# RP_Pico.net
KiCad netlist of a schematic drawn in Altium Designer
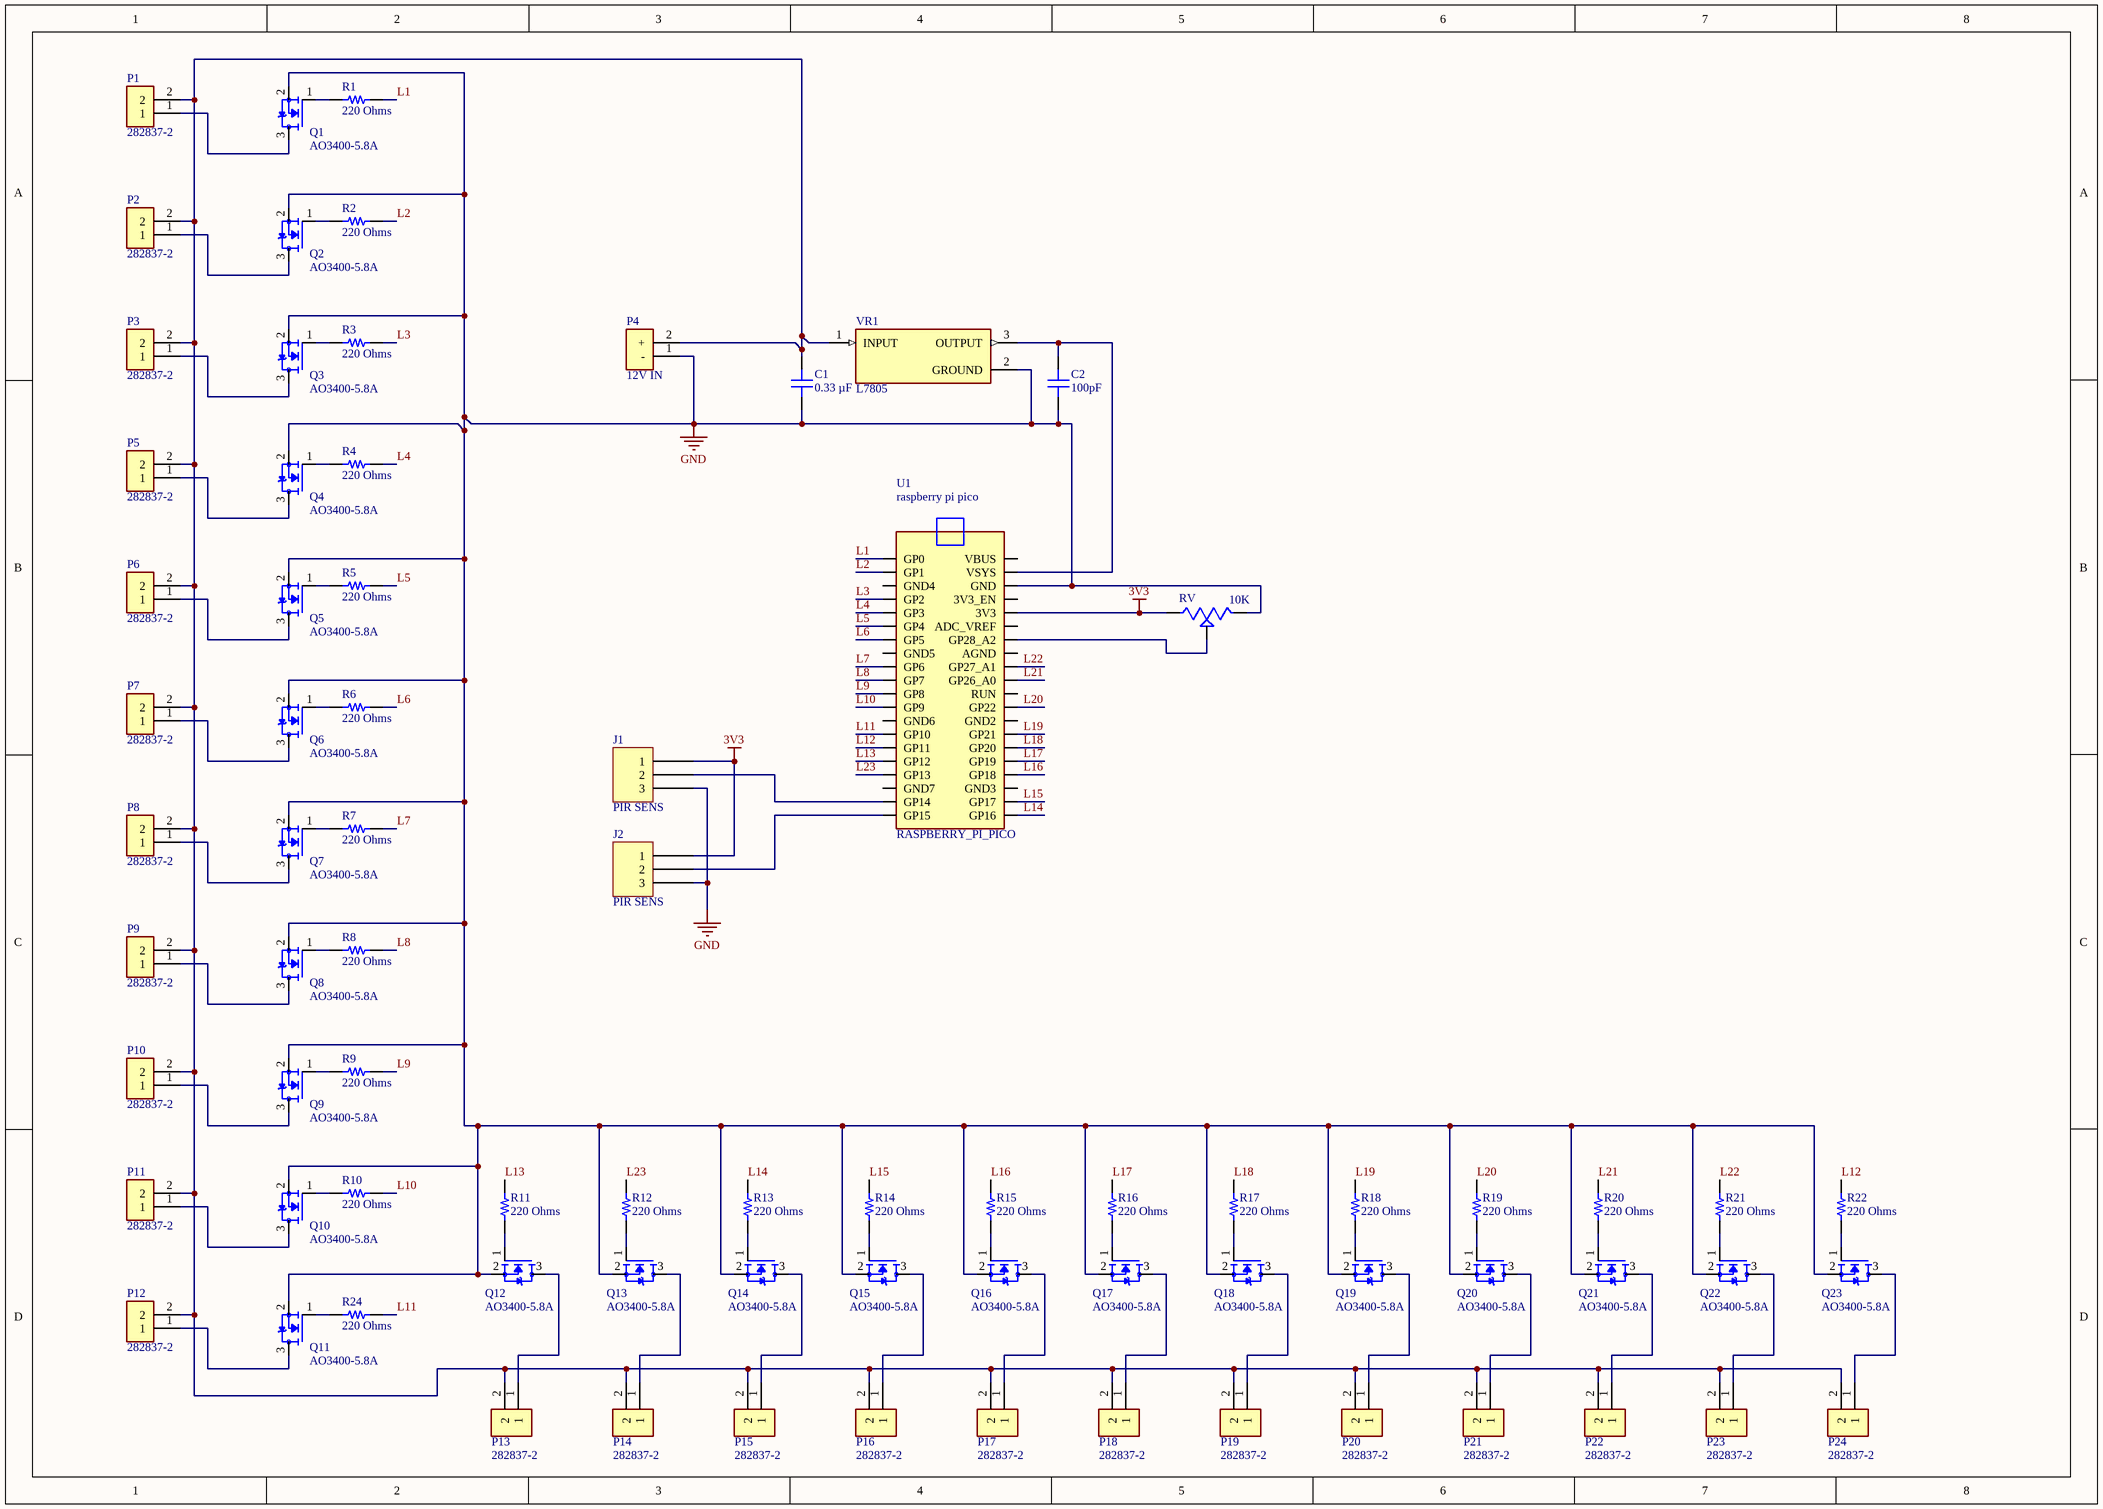
[diagram p0: RP Pico.SchDoc]

(export (version "E")
  (design (tool "Eeschema 10.0.6"))
  (components
    (comp (ref "C1")
      (value "0.33 µF")
      (footprint "CAP 1206_3216 - 0.8MM")
      (description "CAP CER 0.33UF 25V X7R 1206")
      (fields
        (field (name "PART NUMBER") "CC1206JKX7R8BB334")
        (field (name "CAPACITANCE") "0.33 µF")
        (field (name "MANUFACTURER") "Yageo")
      )
      (libsource (lib "Celestial Altium Library - altium_library") (part "Capacitor"))
    )
    (comp (ref "C2")
      (value "100pF")
      (footprint "CAP 1206_3216 - 0.8MM")
      (description "CAP CER 100PF 100V C0G/NP0 1206")
      (fields
        (field (name "PART NUMBER") "MM061A101JCT2A")
        (field (name "CAPACITANCE") "100pF")
        (field (name "MANUFACTURER") "AVX Corporation")
      )
      (libsource (lib "Celestial Altium Library - altium_library") (part "Capacitor"))
    )
    (comp (ref "J1")
      (value "PIR SENS")
      (footprint "HARWIN M20-7820345")
      (description "CONN RCPT 3POS 0.1 GOLD PCB")
      (fields (field (name "PART NUMBER") "M20-7820342") (field (name "MANUFACTURER") "Harwin Inc."))
      (libsource (lib "Celestial Altium Library - altium_library") (part "3 Pin"))
    )
    (comp (ref "J2")
      (value "PIR SENS")
      (footprint "HARWIN M20-7820345")
      (description "CONN RCPT 3POS 0.1 GOLD PCB")
      (fields (field (name "PART NUMBER") "M20-7820342") (field (name "MANUFACTURER") "Harwin Inc."))
      (libsource (lib "Celestial Altium Library - altium_library") (part "3 Pin"))
    )
    (comp (ref "P1")
      (value "282837-2")
      (footprint "TE_282837-2")
      (fields (field (name "MF") "TE Connectivity"))
      (libsource (lib "2 pin con") (part "282837-2"))
    )
    (comp (ref "P2")
      (value "282837-2")
      (footprint "TE_282837-2")
      (fields (field (name "MF") "TE Connectivity"))
      (libsource (lib "2 pin con") (part "282837-2"))
    )
    (comp (ref "P3")
      (value "282837-2")
      (footprint "TE_282837-2")
      (fields (field (name "MF") "TE Connectivity"))
      (libsource (lib "2 pin con") (part "282837-2"))
    )
    (comp (ref "P4")
      (value "12V IN")
      (footprint "TE_282837-2")
      (fields (field (name "MF") "TE Connectivity") (field (name "MP") "282837-2"))
      (libsource (lib "2 pin con") (part "282837-2"))
    )
    (comp (ref "P5")
      (value "282837-2")
      (footprint "TE_282837-2")
      (fields (field (name "MF") "TE Connectivity"))
      (libsource (lib "2 pin con") (part "282837-2"))
    )
    (comp (ref "P6")
      (value "282837-2")
      (footprint "TE_282837-2")
      (fields (field (name "MF") "TE Connectivity"))
      (libsource (lib "2 pin con") (part "282837-2"))
    )
    (comp (ref "P7")
      (value "282837-2")
      (footprint "TE_282837-2")
      (fields (field (name "MF") "TE Connectivity"))
      (libsource (lib "2 pin con") (part "282837-2"))
    )
    (comp (ref "P8")
      (value "282837-2")
      (footprint "TE_282837-2")
      (fields (field (name "MF") "TE Connectivity"))
      (libsource (lib "2 pin con") (part "282837-2"))
    )
    (comp (ref "P9")
      (value "282837-2")
      (footprint "TE_282837-2")
      (fields (field (name "MF") "TE Connectivity"))
      (libsource (lib "2 pin con") (part "282837-2"))
    )
    (comp (ref "P10")
      (value "282837-2")
      (footprint "TE_282837-2")
      (fields (field (name "MF") "TE Connectivity"))
      (libsource (lib "2 pin con") (part "282837-2"))
    )
    (comp (ref "P11")
      (value "282837-2")
      (footprint "TE_282837-2")
      (fields (field (name "MF") "TE Connectivity"))
      (libsource (lib "2 pin con") (part "282837-2"))
    )
    (comp (ref "P12")
      (value "282837-2")
      (footprint "TE_282837-2")
      (fields (field (name "MF") "TE Connectivity"))
      (libsource (lib "2 pin con") (part "282837-2"))
    )
    (comp (ref "P13")
      (value "282837-2")
      (footprint "TE_282837-2")
      (fields (field (name "MF") "TE Connectivity"))
      (libsource (lib "") (part "282837-2_1"))
    )
    (comp (ref "P14")
      (value "282837-2")
      (footprint "TE_282837-2")
      (fields (field (name "MF") "TE Connectivity"))
      (libsource (lib "") (part "282837-2_1"))
    )
    (comp (ref "P15")
      (value "282837-2")
      (footprint "TE_282837-2")
      (fields (field (name "MF") "TE Connectivity"))
      (libsource (lib "") (part "282837-2_1"))
    )
    (comp (ref "P16")
      (value "282837-2")
      (footprint "TE_282837-2")
      (fields (field (name "MF") "TE Connectivity"))
      (libsource (lib "") (part "282837-2_1"))
    )
    (comp (ref "P17")
      (value "282837-2")
      (footprint "TE_282837-2")
      (fields (field (name "MF") "TE Connectivity"))
      (libsource (lib "") (part "282837-2_1"))
    )
    (comp (ref "P18")
      (value "282837-2")
      (footprint "TE_282837-2")
      (fields (field (name "MF") "TE Connectivity"))
      (libsource (lib "") (part "282837-2_1"))
    )
    (comp (ref "P19")
      (value "282837-2")
      (footprint "TE_282837-2")
      (fields (field (name "MF") "TE Connectivity"))
      (libsource (lib "") (part "282837-2_1"))
    )
    (comp (ref "P20")
      (value "282837-2")
      (footprint "TE_282837-2")
      (fields (field (name "MF") "TE Connectivity"))
      (libsource (lib "") (part "282837-2_1"))
    )
    (comp (ref "P21")
      (value "282837-2")
      (footprint "TE_282837-2")
      (fields (field (name "MF") "TE Connectivity"))
      (libsource (lib "") (part "282837-2_1"))
    )
    (comp (ref "P22")
      (value "282837-2")
      (footprint "TE_282837-2")
      (fields (field (name "MF") "TE Connectivity"))
      (libsource (lib "") (part "282837-2_1"))
    )
    (comp (ref "P23")
      (value "282837-2")
      (footprint "TE_282837-2")
      (fields (field (name "MF") "TE Connectivity"))
      (libsource (lib "") (part "282837-2_1"))
    )
    (comp (ref "P24")
      (value "282837-2")
      (footprint "TE_282837-2")
      (fields (field (name "MF") "TE Connectivity"))
      (libsource (lib "") (part "282837-2_1"))
    )
    (comp (ref "Q1")
      (value "AO3400-5.8A")
      (footprint "SOT95P260X140-3N")
      (description "N-Channel 30 V 5.8A (Ta) 1.5W (Ta) Surface Mount SOT-23")
      (fields (field (name "MF") "MDD"))
      (libsource (lib "AO3400-5.8A") (part "AO3400-5.8A"))
    )
    (comp (ref "Q2")
      (value "AO3400-5.8A")
      (footprint "SOT95P260X140-3N")
      (description "N-Channel 30 V 5.8A (Ta) 1.5W (Ta) Surface Mount SOT-23")
      (fields (field (name "MF") "MDD"))
      (libsource (lib "AO3400-5.8A") (part "AO3400-5.8A"))
    )
    (comp (ref "Q3")
      (value "AO3400-5.8A")
      (footprint "SOT95P260X140-3N")
      (description "N-Channel 30 V 5.8A (Ta) 1.5W (Ta) Surface Mount SOT-23")
      (fields (field (name "MF") "MDD"))
      (libsource (lib "AO3400-5.8A") (part "AO3400-5.8A"))
    )
    (comp (ref "Q4")
      (value "AO3400-5.8A")
      (footprint "SOT95P260X140-3N")
      (description "N-Channel 30 V 5.8A (Ta) 1.5W (Ta) Surface Mount SOT-23")
      (fields (field (name "MF") "MDD"))
      (libsource (lib "AO3400-5.8A") (part "AO3400-5.8A"))
    )
    (comp (ref "Q5")
      (value "AO3400-5.8A")
      (footprint "SOT95P260X140-3N")
      (description "N-Channel 30 V 5.8A (Ta) 1.5W (Ta) Surface Mount SOT-23")
      (fields (field (name "MF") "MDD"))
      (libsource (lib "AO3400-5.8A") (part "AO3400-5.8A"))
    )
    (comp (ref "Q6")
      (value "AO3400-5.8A")
      (footprint "SOT95P260X140-3N")
      (description "N-Channel 30 V 5.8A (Ta) 1.5W (Ta) Surface Mount SOT-23")
      (fields (field (name "MF") "MDD"))
      (libsource (lib "AO3400-5.8A") (part "AO3400-5.8A"))
    )
    (comp (ref "Q7")
      (value "AO3400-5.8A")
      (footprint "SOT95P260X140-3N")
      (description "N-Channel 30 V 5.8A (Ta) 1.5W (Ta) Surface Mount SOT-23")
      (fields (field (name "MF") "MDD"))
      (libsource (lib "AO3400-5.8A") (part "AO3400-5.8A"))
    )
    (comp (ref "Q8")
      (value "AO3400-5.8A")
      (footprint "SOT95P260X140-3N")
      (description "N-Channel 30 V 5.8A (Ta) 1.5W (Ta) Surface Mount SOT-23")
      (fields (field (name "MF") "MDD"))
      (libsource (lib "AO3400-5.8A") (part "AO3400-5.8A"))
    )
    (comp (ref "Q9")
      (value "AO3400-5.8A")
      (footprint "SOT95P260X140-3N")
      (description "N-Channel 30 V 5.8A (Ta) 1.5W (Ta) Surface Mount SOT-23")
      (fields (field (name "MF") "MDD"))
      (libsource (lib "AO3400-5.8A") (part "AO3400-5.8A"))
    )
    (comp (ref "Q10")
      (value "AO3400-5.8A")
      (footprint "SOT95P260X140-3N")
      (description "N-Channel 30 V 5.8A (Ta) 1.5W (Ta) Surface Mount SOT-23")
      (fields (field (name "MF") "MDD"))
      (libsource (lib "AO3400-5.8A") (part "AO3400-5.8A"))
    )
    (comp (ref "Q11")
      (value "AO3400-5.8A")
      (footprint "SOT95P260X140-3N")
      (description "N-Channel 30 V 5.8A (Ta) 1.5W (Ta) Surface Mount SOT-23")
      (fields (field (name "MF") "MDD"))
      (libsource (lib "AO3400-5.8A") (part "AO3400-5.8A"))
    )
    (comp (ref "Q12")
      (value "AO3400-5.8A")
      (footprint "SOT95P260X140-3N")
      (description "N-Channel 30 V 5.8A (Ta) 1.5W (Ta) Surface Mount SOT-23")
      (fields (field (name "MF") "MDD"))
      (libsource (lib "AO3400-5.8A") (part "AO3400-5.8A"))
    )
    (comp (ref "Q13")
      (value "AO3400-5.8A")
      (footprint "SOT95P260X140-3N")
      (description "N-Channel 30 V 5.8A (Ta) 1.5W (Ta) Surface Mount SOT-23")
      (fields (field (name "MF") "MDD"))
      (libsource (lib "AO3400-5.8A") (part "AO3400-5.8A"))
    )
    (comp (ref "Q14")
      (value "AO3400-5.8A")
      (footprint "SOT95P260X140-3N")
      (description "N-Channel 30 V 5.8A (Ta) 1.5W (Ta) Surface Mount SOT-23")
      (fields (field (name "MF") "MDD"))
      (libsource (lib "AO3400-5.8A") (part "AO3400-5.8A"))
    )
    (comp (ref "Q15")
      (value "AO3400-5.8A")
      (footprint "SOT95P260X140-3N")
      (description "N-Channel 30 V 5.8A (Ta) 1.5W (Ta) Surface Mount SOT-23")
      (fields (field (name "MF") "MDD"))
      (libsource (lib "AO3400-5.8A") (part "AO3400-5.8A"))
    )
    (comp (ref "Q16")
      (value "AO3400-5.8A")
      (footprint "SOT95P260X140-3N")
      (description "N-Channel 30 V 5.8A (Ta) 1.5W (Ta) Surface Mount SOT-23")
      (fields (field (name "MF") "MDD"))
      (libsource (lib "AO3400-5.8A") (part "AO3400-5.8A"))
    )
    (comp (ref "Q17")
      (value "AO3400-5.8A")
      (footprint "SOT95P260X140-3N")
      (description "N-Channel 30 V 5.8A (Ta) 1.5W (Ta) Surface Mount SOT-23")
      (fields (field (name "MF") "MDD"))
      (libsource (lib "AO3400-5.8A") (part "AO3400-5.8A"))
    )
    (comp (ref "Q18")
      (value "AO3400-5.8A")
      (footprint "SOT95P260X140-3N")
      (description "N-Channel 30 V 5.8A (Ta) 1.5W (Ta) Surface Mount SOT-23")
      (fields (field (name "MF") "MDD"))
      (libsource (lib "AO3400-5.8A") (part "AO3400-5.8A"))
    )
    (comp (ref "Q19")
      (value "AO3400-5.8A")
      (footprint "SOT95P260X140-3N")
      (description "N-Channel 30 V 5.8A (Ta) 1.5W (Ta) Surface Mount SOT-23")
      (fields (field (name "MF") "MDD"))
      (libsource (lib "AO3400-5.8A") (part "AO3400-5.8A"))
    )
    (comp (ref "Q20")
      (value "AO3400-5.8A")
      (footprint "SOT95P260X140-3N")
      (description "N-Channel 30 V 5.8A (Ta) 1.5W (Ta) Surface Mount SOT-23")
      (fields (field (name "MF") "MDD"))
      (libsource (lib "AO3400-5.8A") (part "AO3400-5.8A"))
    )
    (comp (ref "Q21")
      (value "AO3400-5.8A")
      (footprint "SOT95P260X140-3N")
      (description "N-Channel 30 V 5.8A (Ta) 1.5W (Ta) Surface Mount SOT-23")
      (fields (field (name "MF") "MDD"))
      (libsource (lib "AO3400-5.8A") (part "AO3400-5.8A"))
    )
    (comp (ref "Q22")
      (value "AO3400-5.8A")
      (footprint "SOT95P260X140-3N")
      (description "N-Channel 30 V 5.8A (Ta) 1.5W (Ta) Surface Mount SOT-23")
      (fields (field (name "MF") "MDD"))
      (libsource (lib "AO3400-5.8A") (part "AO3400-5.8A"))
    )
    (comp (ref "Q23")
      (value "AO3400-5.8A")
      (footprint "SOT95P260X140-3N")
      (description "N-Channel 30 V 5.8A (Ta) 1.5W (Ta) Surface Mount SOT-23")
      (fields (field (name "MF") "MDD"))
      (libsource (lib "AO3400-5.8A") (part "AO3400-5.8A"))
    )
    (comp (ref "R1")
      (value "220 Ohms")
      (footprint "YAGEO RES 1206_3216")
      (description "RES SMD 220 OHM 5% 1/4W 1206")
      (fields (field (name "PART NUMBER") "AC1206JR-07220RL") (field (name "MANUFACTURER") "Yageo"))
      (libsource (lib "Celestial Altium Library - altium_library") (part "Resistor"))
    )
    (comp (ref "R2")
      (value "220 Ohms")
      (footprint "YAGEO RES 1206_3216")
      (description "RES SMD 220 OHM 5% 1/4W 1206")
      (fields (field (name "PART NUMBER") "AC1206JR-07220RL") (field (name "MANUFACTURER") "Yageo"))
      (libsource (lib "Celestial Altium Library - altium_library") (part "Resistor"))
    )
    (comp (ref "R3")
      (value "220 Ohms")
      (footprint "YAGEO RES 1206_3216")
      (description "RES SMD 220 OHM 5% 1/4W 1206")
      (fields (field (name "PART NUMBER") "AC1206JR-07220RL") (field (name "MANUFACTURER") "Yageo"))
      (libsource (lib "Celestial Altium Library - altium_library") (part "Resistor"))
    )
    (comp (ref "R4")
      (value "220 Ohms")
      (footprint "YAGEO RES 1206_3216")
      (description "RES SMD 220 OHM 5% 1/4W 1206")
      (fields (field (name "PART NUMBER") "AC1206JR-07220RL") (field (name "MANUFACTURER") "Yageo"))
      (libsource (lib "Celestial Altium Library - altium_library") (part "Resistor"))
    )
    (comp (ref "R5")
      (value "220 Ohms")
      (footprint "YAGEO RES 1206_3216")
      (description "RES SMD 220 OHM 5% 1/4W 1206")
      (fields (field (name "PART NUMBER") "AC1206JR-07220RL") (field (name "MANUFACTURER") "Yageo"))
      (libsource (lib "Celestial Altium Library - altium_library") (part "Resistor"))
    )
    (comp (ref "R6")
      (value "220 Ohms")
      (footprint "YAGEO RES 1206_3216")
      (description "RES SMD 220 OHM 5% 1/4W 1206")
      (fields (field (name "PART NUMBER") "AC1206JR-07220RL") (field (name "MANUFACTURER") "Yageo"))
      (libsource (lib "Celestial Altium Library - altium_library") (part "Resistor"))
    )
    (comp (ref "R7")
      (value "220 Ohms")
      (footprint "YAGEO RES 1206_3216")
      (description "RES SMD 220 OHM 5% 1/4W 1206")
      (fields (field (name "PART NUMBER") "AC1206JR-07220RL") (field (name "MANUFACTURER") "Yageo"))
      (libsource (lib "Celestial Altium Library - altium_library") (part "Resistor"))
    )
    (comp (ref "R8")
      (value "220 Ohms")
      (footprint "YAGEO RES 1206_3216")
      (description "RES SMD 220 OHM 5% 1/4W 1206")
      (fields (field (name "PART NUMBER") "AC1206JR-07220RL") (field (name "MANUFACTURER") "Yageo"))
      (libsource (lib "Celestial Altium Library - altium_library") (part "Resistor"))
    )
    (comp (ref "R9")
      (value "220 Ohms")
      (footprint "YAGEO RES 1206_3216")
      (description "RES SMD 220 OHM 5% 1/4W 1206")
      (fields (field (name "PART NUMBER") "AC1206JR-07220RL") (field (name "MANUFACTURER") "Yageo"))
      (libsource (lib "Celestial Altium Library - altium_library") (part "Resistor"))
    )
    (comp (ref "R10")
      (value "220 Ohms")
      (footprint "YAGEO RES 1206_3216")
      (description "RES SMD 220 OHM 5% 1/4W 1206")
      (fields (field (name "PART NUMBER") "AC1206JR-07220RL") (field (name "MANUFACTURER") "Yageo"))
      (libsource (lib "Celestial Altium Library - altium_library") (part "Resistor"))
    )
    (comp (ref "R11")
      (value "220 Ohms")
      (footprint "YAGEO RES 1206_3216")
      (description "RES SMD 220 OHM 5% 1/4W 1206")
      (fields (field (name "PART NUMBER") "AC1206JR-07220RL") (field (name "MANUFACTURER") "Yageo"))
      (libsource (lib "Celestial Altium Library - altium_library") (part "Resistor"))
    )
    (comp (ref "R12")
      (value "220 Ohms")
      (footprint "YAGEO RES 1206_3216")
      (description "RES SMD 220 OHM 5% 1/4W 1206")
      (fields (field (name "PART NUMBER") "AC1206JR-07220RL") (field (name "MANUFACTURER") "Yageo"))
      (libsource (lib "Celestial Altium Library - altium_library") (part "Resistor"))
    )
    (comp (ref "R13")
      (value "220 Ohms")
      (footprint "YAGEO RES 1206_3216")
      (description "RES SMD 220 OHM 5% 1/4W 1206")
      (fields (field (name "PART NUMBER") "AC1206JR-07220RL") (field (name "MANUFACTURER") "Yageo"))
      (libsource (lib "Celestial Altium Library - altium_library") (part "Resistor"))
    )
    (comp (ref "R14")
      (value "220 Ohms")
      (footprint "YAGEO RES 1206_3216")
      (description "RES SMD 220 OHM 5% 1/4W 1206")
      (fields (field (name "PART NUMBER") "AC1206JR-07220RL") (field (name "MANUFACTURER") "Yageo"))
      (libsource (lib "Celestial Altium Library - altium_library") (part "Resistor"))
    )
    (comp (ref "R15")
      (value "220 Ohms")
      (footprint "YAGEO RES 1206_3216")
      (description "RES SMD 220 OHM 5% 1/4W 1206")
      (fields (field (name "PART NUMBER") "AC1206JR-07220RL") (field (name "MANUFACTURER") "Yageo"))
      (libsource (lib "Celestial Altium Library - altium_library") (part "Resistor"))
    )
    (comp (ref "R16")
      (value "220 Ohms")
      (footprint "YAGEO RES 1206_3216")
      (description "RES SMD 220 OHM 5% 1/4W 1206")
      (fields (field (name "PART NUMBER") "AC1206JR-07220RL") (field (name "MANUFACTURER") "Yageo"))
      (libsource (lib "Celestial Altium Library - altium_library") (part "Resistor"))
    )
    (comp (ref "R17")
      (value "220 Ohms")
      (footprint "YAGEO RES 1206_3216")
      (description "RES SMD 220 OHM 5% 1/4W 1206")
      (fields (field (name "PART NUMBER") "AC1206JR-07220RL") (field (name "MANUFACTURER") "Yageo"))
      (libsource (lib "Celestial Altium Library - altium_library") (part "Resistor"))
    )
    (comp (ref "R18")
      (value "220 Ohms")
      (footprint "YAGEO RES 1206_3216")
      (description "RES SMD 220 OHM 5% 1/4W 1206")
      (fields (field (name "PART NUMBER") "AC1206JR-07220RL") (field (name "MANUFACTURER") "Yageo"))
      (libsource (lib "Celestial Altium Library - altium_library") (part "Resistor"))
    )
    (comp (ref "R19")
      (value "220 Ohms")
      (footprint "YAGEO RES 1206_3216")
      (description "RES SMD 220 OHM 5% 1/4W 1206")
      (fields (field (name "PART NUMBER") "AC1206JR-07220RL") (field (name "MANUFACTURER") "Yageo"))
      (libsource (lib "Celestial Altium Library - altium_library") (part "Resistor"))
    )
    (comp (ref "R20")
      (value "220 Ohms")
      (footprint "YAGEO RES 1206_3216")
      (description "RES SMD 220 OHM 5% 1/4W 1206")
      (fields (field (name "PART NUMBER") "AC1206JR-07220RL") (field (name "MANUFACTURER") "Yageo"))
      (libsource (lib "Celestial Altium Library - altium_library") (part "Resistor"))
    )
    (comp (ref "R21")
      (value "220 Ohms")
      (footprint "YAGEO RES 1206_3216")
      (description "RES SMD 220 OHM 5% 1/4W 1206")
      (fields (field (name "PART NUMBER") "AC1206JR-07220RL") (field (name "MANUFACTURER") "Yageo"))
      (libsource (lib "Celestial Altium Library - altium_library") (part "Resistor"))
    )
    (comp (ref "R22")
      (value "220 Ohms")
      (footprint "YAGEO RES 1206_3216")
      (description "RES SMD 220 OHM 5% 1/4W 1206")
      (fields (field (name "PART NUMBER") "AC1206JR-07220RL") (field (name "MANUFACTURER") "Yageo"))
      (libsource (lib "Celestial Altium Library - altium_library") (part "Resistor"))
    )
    (comp (ref "R24")
      (value "220 Ohms")
      (footprint "YAGEO RES 1206_3216")
      (description "RES SMD 220 OHM 5% 1/4W 1206")
      (fields (field (name "PART NUMBER") "AC1206JR-07220RL") (field (name "MANUFACTURER") "Yageo"))
      (libsource (lib "Celestial Altium Library - altium_library") (part "Resistor"))
    )
    (comp (ref "RV")
      (value "10K")
      (footprint "TRIM_PTN06-D02CB20")
      (fields (field (name "MP") "PTN06-D02CB20"))
      (libsource (lib "PTN06-D02CB20") (part "PTN06-D02CB20"))
    )
    (comp (ref "U1")
      (value "RASPBERRY_PI_PICO")
      (footprint "RASPBERRY_PI_PICO")
      (fields (field (name "MF") "Raspberry Pi") (field (name "MP") "RASPBERRY PI PICO"))
      (libsource (lib "RASPBERRY_PI_PICO") (part "RASPBERRY_PI_PICO"))
    )
    (comp (ref "VR1")
      (value "L7805")
      (footprint "TO255P1020X450X2000-3")
      (description "Standard Regulator Pos 5V 1.5A 3-Pin(3+Tab) TO-220FP Tube")
      (fields (field (name "MF") "STMicroelectronics"))
      (libsource (lib "L7805") (part "L7805"))
    )
  )
  (nets
    (net (code "1") (name "/L1") (class "Default")
      (node (ref "R1") (pin "2") (pinfunction "2_2") (pintype "passive"))
      (node (ref "U1") (pin "GP0") (pinfunction "GP0_GP0") (pintype "bidirectional"))
    )
    (net (code "2") (name "/L2") (class "Default")
      (node (ref "R2") (pin "2") (pinfunction "2_2") (pintype "passive"))
      (node (ref "U1") (pin "GP1") (pinfunction "GP1_GP1") (pintype "bidirectional"))
    )
    (net (code "3") (name "/L3") (class "Default")
      (node (ref "R3") (pin "2") (pinfunction "2_2") (pintype "passive"))
      (node (ref "U1") (pin "GP2") (pinfunction "GP2_GP2") (pintype "bidirectional"))
    )
    (net (code "4") (name "/L4") (class "Default")
      (node (ref "R4") (pin "2") (pinfunction "2_2") (pintype "passive"))
      (node (ref "U1") (pin "GP3") (pinfunction "GP3_GP3") (pintype "bidirectional"))
    )
    (net (code "5") (name "/L5") (class "Default")
      (node (ref "R5") (pin "2") (pinfunction "2_2") (pintype "passive"))
      (node (ref "U1") (pin "GP4") (pinfunction "GP4_GP4") (pintype "bidirectional"))
    )
    (net (code "6") (name "/L6") (class "Default")
      (node (ref "R6") (pin "2") (pinfunction "2_2") (pintype "passive"))
      (node (ref "U1") (pin "GP5") (pinfunction "GP5_GP5") (pintype "bidirectional"))
    )
    (net (code "7") (name "/L7") (class "Default")
      (node (ref "R7") (pin "2") (pinfunction "2_2") (pintype "passive"))
      (node (ref "U1") (pin "GP6") (pinfunction "GP6_GP6") (pintype "bidirectional"))
    )
    (net (code "8") (name "/L8") (class "Default")
      (node (ref "R8") (pin "2") (pinfunction "2_2") (pintype "passive"))
      (node (ref "U1") (pin "GP7") (pinfunction "GP7_GP7") (pintype "bidirectional"))
    )
    (net (code "9") (name "/L9") (class "Default")
      (node (ref "R9") (pin "2") (pinfunction "2_2") (pintype "passive"))
      (node (ref "U1") (pin "GP8") (pinfunction "GP8_GP8") (pintype "bidirectional"))
    )
    (net (code "10") (name "/L10") (class "Default")
      (node (ref "R10") (pin "2") (pinfunction "2_2") (pintype "passive"))
      (node (ref "U1") (pin "GP9") (pinfunction "GP9_GP9") (pintype "bidirectional"))
    )
    (net (code "11") (name "/L11") (class "Default")
      (node (ref "R24") (pin "2") (pinfunction "2_2") (pintype "passive"))
      (node (ref "U1") (pin "GP10") (pinfunction "GP10_GP10") (pintype "bidirectional"))
    )
    (net (code "12") (name "/L12") (class "Default")
      (node (ref "R22") (pin "2") (pinfunction "2_2") (pintype "passive"))
      (node (ref "U1") (pin "GP11") (pinfunction "GP11_GP11") (pintype "bidirectional"))
    )
    (net (code "13") (name "/L13") (class "Default")
      (node (ref "R11") (pin "2") (pinfunction "2_2") (pintype "passive"))
      (node (ref "U1") (pin "GP12") (pinfunction "GP12_GP12") (pintype "bidirectional"))
    )
    (net (code "14") (name "/L14") (class "Default")
      (node (ref "R13") (pin "2") (pinfunction "2_2") (pintype "passive"))
      (node (ref "U1") (pin "GP16") (pinfunction "GP16_GP16") (pintype "bidirectional"))
    )
    (net (code "15") (name "/L15") (class "Default")
      (node (ref "R14") (pin "2") (pinfunction "2_2") (pintype "passive"))
      (node (ref "U1") (pin "GP17") (pinfunction "GP17_GP17") (pintype "bidirectional"))
    )
    (net (code "16") (name "/L16") (class "Default")
      (node (ref "R15") (pin "2") (pinfunction "2_2") (pintype "passive"))
      (node (ref "U1") (pin "GP18") (pinfunction "GP18_GP18") (pintype "bidirectional"))
    )
    (net (code "17") (name "/L17") (class "Default")
      (node (ref "R16") (pin "2") (pinfunction "2_2") (pintype "passive"))
      (node (ref "U1") (pin "GP19") (pinfunction "GP19_GP19") (pintype "bidirectional"))
    )
    (net (code "18") (name "/L18") (class "Default")
      (node (ref "R17") (pin "2") (pinfunction "2_2") (pintype "passive"))
      (node (ref "U1") (pin "GP20") (pinfunction "GP20_GP20") (pintype "bidirectional"))
    )
    (net (code "19") (name "/L19") (class "Default")
      (node (ref "R18") (pin "2") (pinfunction "2_2") (pintype "passive"))
      (node (ref "U1") (pin "GP21") (pinfunction "GP21_GP21") (pintype "bidirectional"))
    )
    (net (code "20") (name "/L20") (class "Default")
      (node (ref "R19") (pin "2") (pinfunction "2_2") (pintype "passive"))
      (node (ref "U1") (pin "GP22") (pinfunction "GP22_GP22") (pintype "bidirectional"))
    )
    (net (code "21") (name "/L21") (class "Default")
      (node (ref "R20") (pin "2") (pinfunction "2_2") (pintype "passive"))
      (node (ref "U1") (pin "GP26_A0") (pinfunction "GP26_A0_GP26_A0") (pintype "bidirectional"))
    )
    (net (code "22") (name "/L22") (class "Default")
      (node (ref "R21") (pin "2") (pinfunction "2_2") (pintype "passive"))
      (node (ref "U1") (pin "GP27_A1") (pinfunction "GP27_A1_GP27_A1") (pintype "bidirectional"))
    )
    (net (code "23") (name "/L23") (class "Default")
      (node (ref "R12") (pin "2") (pinfunction "2_2") (pintype "passive"))
      (node (ref "U1") (pin "GP13") (pinfunction "GP13_GP13") (pintype "bidirectional"))
    )
    (net (code "24") (name "3V3") (class "Default")
      (node (ref "J1") (pin "1") (pinfunction "1_1") (pintype "passive"))
      (node (ref "J2") (pin "1") (pinfunction "1_1") (pintype "passive"))
      (node (ref "RV") (pin "1") (pinfunction "INITIAL_1") (pintype "passive"))
      (node (ref "U1") (pin "3V3") (pinfunction "3V3_3V3") (pintype "bidirectional"))
    )
    (net (code "25") (name "GND") (class "Default")
      (node (ref "C1") (pin "1") (pinfunction "1_1") (pintype "passive"))
      (node (ref "C2") (pin "2") (pinfunction "2_2") (pintype "passive"))
      (node (ref "J1") (pin "3") (pinfunction "3_3") (pintype "passive"))
      (node (ref "J2") (pin "3") (pinfunction "3_3") (pintype "passive"))
      (node (ref "P4") (pin "1") (pinfunction "1_1") (pintype "passive"))
      (node (ref "Q1") (pin "2") (pinfunction "S_2") (pintype "passive"))
      (node (ref "Q10") (pin "2") (pinfunction "S_2") (pintype "passive"))
      (node (ref "Q11") (pin "2") (pinfunction "S_2") (pintype "passive"))
      (node (ref "Q12") (pin "2") (pinfunction "S_2") (pintype "passive"))
      (node (ref "Q13") (pin "2") (pinfunction "S_2") (pintype "passive"))
      (node (ref "Q14") (pin "2") (pinfunction "S_2") (pintype "passive"))
      (node (ref "Q15") (pin "2") (pinfunction "S_2") (pintype "passive"))
      (node (ref "Q16") (pin "2") (pinfunction "S_2") (pintype "passive"))
      (node (ref "Q17") (pin "2") (pinfunction "S_2") (pintype "passive"))
      (node (ref "Q18") (pin "2") (pinfunction "S_2") (pintype "passive"))
      (node (ref "Q19") (pin "2") (pinfunction "S_2") (pintype "passive"))
      (node (ref "Q2") (pin "2") (pinfunction "S_2") (pintype "passive"))
      (node (ref "Q20") (pin "2") (pinfunction "S_2") (pintype "passive"))
      (node (ref "Q21") (pin "2") (pinfunction "S_2") (pintype "passive"))
      (node (ref "Q22") (pin "2") (pinfunction "S_2") (pintype "passive"))
      (node (ref "Q23") (pin "2") (pinfunction "S_2") (pintype "passive"))
      (node (ref "Q3") (pin "2") (pinfunction "S_2") (pintype "passive"))
      (node (ref "Q4") (pin "2") (pinfunction "S_2") (pintype "passive"))
      (node (ref "Q5") (pin "2") (pinfunction "S_2") (pintype "passive"))
      (node (ref "Q6") (pin "2") (pinfunction "S_2") (pintype "passive"))
      (node (ref "Q7") (pin "2") (pinfunction "S_2") (pintype "passive"))
      (node (ref "Q8") (pin "2") (pinfunction "S_2") (pintype "passive"))
      (node (ref "Q9") (pin "2") (pinfunction "S_2") (pintype "passive"))
      (node (ref "RV") (pin "3") (pinfunction "FINAL_3") (pintype "passive"))
      (node (ref "U1") (pin "GND") (pinfunction "GND_GND") (pintype "bidirectional"))
      (node (ref "VR1") (pin "2") (pinfunction "GROUND_2") (pintype "power_in"))
    )
    (net (code "26") (name "Net-(J1-Pad2)") (class "Default")
      (node (ref "J1") (pin "2") (pinfunction "2_2") (pintype "passive"))
      (node (ref "U1") (pin "GP14") (pinfunction "GP14_GP14") (pintype "bidirectional"))
    )
    (net (code "27") (name "Net-(J2-Pad2)") (class "Default")
      (node (ref "J2") (pin "2") (pinfunction "2_2") (pintype "passive"))
      (node (ref "U1") (pin "GP15") (pinfunction "GP15_GP15") (pintype "bidirectional"))
    )
    (net (code "28") (name "Net-(Q1-D)") (class "Default")
      (node (ref "P1") (pin "1") (pinfunction "1_1") (pintype "passive"))
      (node (ref "Q1") (pin "3") (pinfunction "D_3") (pintype "passive"))
    )
    (net (code "29") (name "Net-(Q1-G)") (class "Default")
      (node (ref "Q1") (pin "1") (pinfunction "G_1") (pintype "passive"))
      (node (ref "R1") (pin "1") (pinfunction "1_1") (pintype "passive"))
    )
    (net (code "30") (name "Net-(Q2-D)") (class "Default")
      (node (ref "P2") (pin "1") (pinfunction "1_1") (pintype "passive"))
      (node (ref "Q2") (pin "3") (pinfunction "D_3") (pintype "passive"))
    )
    (net (code "31") (name "Net-(Q2-G)") (class "Default")
      (node (ref "Q2") (pin "1") (pinfunction "G_1") (pintype "passive"))
      (node (ref "R2") (pin "1") (pinfunction "1_1") (pintype "passive"))
    )
    (net (code "32") (name "Net-(Q3-D)") (class "Default")
      (node (ref "P3") (pin "1") (pinfunction "1_1") (pintype "passive"))
      (node (ref "Q3") (pin "3") (pinfunction "D_3") (pintype "passive"))
    )
    (net (code "33") (name "Net-(Q3-G)") (class "Default")
      (node (ref "Q3") (pin "1") (pinfunction "G_1") (pintype "passive"))
      (node (ref "R3") (pin "1") (pinfunction "1_1") (pintype "passive"))
    )
    (net (code "34") (name "Net-(Q4-D)") (class "Default")
      (node (ref "P5") (pin "1") (pinfunction "1_1") (pintype "passive"))
      (node (ref "Q4") (pin "3") (pinfunction "D_3") (pintype "passive"))
    )
    (net (code "35") (name "Net-(Q4-G)") (class "Default")
      (node (ref "Q4") (pin "1") (pinfunction "G_1") (pintype "passive"))
      (node (ref "R4") (pin "1") (pinfunction "1_1") (pintype "passive"))
    )
    (net (code "36") (name "Net-(Q5-D)") (class "Default")
      (node (ref "P6") (pin "1") (pinfunction "1_1") (pintype "passive"))
      (node (ref "Q5") (pin "3") (pinfunction "D_3") (pintype "passive"))
    )
    (net (code "37") (name "Net-(Q5-G)") (class "Default")
      (node (ref "Q5") (pin "1") (pinfunction "G_1") (pintype "passive"))
      (node (ref "R5") (pin "1") (pinfunction "1_1") (pintype "passive"))
    )
    (net (code "38") (name "Net-(Q6-D)") (class "Default")
      (node (ref "P7") (pin "1") (pinfunction "1_1") (pintype "passive"))
      (node (ref "Q6") (pin "3") (pinfunction "D_3") (pintype "passive"))
    )
    (net (code "39") (name "Net-(Q6-G)") (class "Default")
      (node (ref "Q6") (pin "1") (pinfunction "G_1") (pintype "passive"))
      (node (ref "R6") (pin "1") (pinfunction "1_1") (pintype "passive"))
    )
    (net (code "40") (name "Net-(Q7-D)") (class "Default")
      (node (ref "P8") (pin "1") (pinfunction "1_1") (pintype "passive"))
      (node (ref "Q7") (pin "3") (pinfunction "D_3") (pintype "passive"))
    )
    (net (code "41") (name "Net-(Q7-G)") (class "Default")
      (node (ref "Q7") (pin "1") (pinfunction "G_1") (pintype "passive"))
      (node (ref "R7") (pin "1") (pinfunction "1_1") (pintype "passive"))
    )
    (net (code "42") (name "Net-(Q8-D)") (class "Default")
      (node (ref "P9") (pin "1") (pinfunction "1_1") (pintype "passive"))
      (node (ref "Q8") (pin "3") (pinfunction "D_3") (pintype "passive"))
    )
    (net (code "43") (name "Net-(Q8-G)") (class "Default")
      (node (ref "Q8") (pin "1") (pinfunction "G_1") (pintype "passive"))
      (node (ref "R8") (pin "1") (pinfunction "1_1") (pintype "passive"))
    )
    (net (code "44") (name "Net-(Q9-D)") (class "Default")
      (node (ref "P10") (pin "1") (pinfunction "1_1") (pintype "passive"))
      (node (ref "Q9") (pin "3") (pinfunction "D_3") (pintype "passive"))
    )
    (net (code "45") (name "Net-(Q9-G)") (class "Default")
      (node (ref "Q9") (pin "1") (pinfunction "G_1") (pintype "passive"))
      (node (ref "R9") (pin "1") (pinfunction "1_1") (pintype "passive"))
    )
    (net (code "46") (name "Net-(Q10-D)") (class "Default")
      (node (ref "P11") (pin "1") (pinfunction "1_1") (pintype "passive"))
      (node (ref "Q10") (pin "3") (pinfunction "D_3") (pintype "passive"))
    )
    (net (code "47") (name "Net-(Q10-G)") (class "Default")
      (node (ref "Q10") (pin "1") (pinfunction "G_1") (pintype "passive"))
      (node (ref "R10") (pin "1") (pinfunction "1_1") (pintype "passive"))
    )
    (net (code "48") (name "Net-(Q11-D)") (class "Default")
      (node (ref "P12") (pin "1") (pinfunction "1_1") (pintype "passive"))
      (node (ref "Q11") (pin "3") (pinfunction "D_3") (pintype "passive"))
    )
    (net (code "49") (name "Net-(Q11-G)") (class "Default")
      (node (ref "Q11") (pin "1") (pinfunction "G_1") (pintype "passive"))
      (node (ref "R24") (pin "1") (pinfunction "1_1") (pintype "passive"))
    )
    (net (code "50") (name "Net-(Q12-D)") (class "Default")
      (node (ref "P13") (pin "1") (pinfunction "1_1") (pintype "passive"))
      (node (ref "Q12") (pin "3") (pinfunction "D_3") (pintype "passive"))
    )
    (net (code "51") (name "Net-(Q12-G)") (class "Default")
      (node (ref "Q12") (pin "1") (pinfunction "G_1") (pintype "passive"))
      (node (ref "R11") (pin "1") (pinfunction "1_1") (pintype "passive"))
    )
    (net (code "52") (name "Net-(Q13-D)") (class "Default")
      (node (ref "P14") (pin "1") (pinfunction "1_1") (pintype "passive"))
      (node (ref "Q13") (pin "3") (pinfunction "D_3") (pintype "passive"))
    )
    (net (code "53") (name "Net-(Q13-G)") (class "Default")
      (node (ref "Q13") (pin "1") (pinfunction "G_1") (pintype "passive"))
      (node (ref "R12") (pin "1") (pinfunction "1_1") (pintype "passive"))
    )
    (net (code "54") (name "Net-(Q14-D)") (class "Default")
      (node (ref "P15") (pin "1") (pinfunction "1_1") (pintype "passive"))
      (node (ref "Q14") (pin "3") (pinfunction "D_3") (pintype "passive"))
    )
    (net (code "55") (name "Net-(Q14-G)") (class "Default")
      (node (ref "Q14") (pin "1") (pinfunction "G_1") (pintype "passive"))
      (node (ref "R13") (pin "1") (pinfunction "1_1") (pintype "passive"))
    )
    (net (code "56") (name "Net-(Q15-D)") (class "Default")
      (node (ref "P16") (pin "1") (pinfunction "1_1") (pintype "passive"))
      (node (ref "Q15") (pin "3") (pinfunction "D_3") (pintype "passive"))
    )
    (net (code "57") (name "Net-(Q15-G)") (class "Default")
      (node (ref "Q15") (pin "1") (pinfunction "G_1") (pintype "passive"))
      (node (ref "R14") (pin "1") (pinfunction "1_1") (pintype "passive"))
    )
    (net (code "58") (name "Net-(Q16-D)") (class "Default")
      (node (ref "P17") (pin "1") (pinfunction "1_1") (pintype "passive"))
      (node (ref "Q16") (pin "3") (pinfunction "D_3") (pintype "passive"))
    )
    (net (code "59") (name "Net-(Q16-G)") (class "Default")
      (node (ref "Q16") (pin "1") (pinfunction "G_1") (pintype "passive"))
      (node (ref "R15") (pin "1") (pinfunction "1_1") (pintype "passive"))
    )
    (net (code "60") (name "Net-(Q17-D)") (class "Default")
      (node (ref "P18") (pin "1") (pinfunction "1_1") (pintype "passive"))
      (node (ref "Q17") (pin "3") (pinfunction "D_3") (pintype "passive"))
    )
    (net (code "61") (name "Net-(Q17-G)") (class "Default")
      (node (ref "Q17") (pin "1") (pinfunction "G_1") (pintype "passive"))
      (node (ref "R16") (pin "1") (pinfunction "1_1") (pintype "passive"))
    )
    (net (code "62") (name "Net-(Q18-D)") (class "Default")
      (node (ref "P19") (pin "1") (pinfunction "1_1") (pintype "passive"))
      (node (ref "Q18") (pin "3") (pinfunction "D_3") (pintype "passive"))
    )
    (net (code "63") (name "Net-(Q18-G)") (class "Default")
      (node (ref "Q18") (pin "1") (pinfunction "G_1") (pintype "passive"))
      (node (ref "R17") (pin "1") (pinfunction "1_1") (pintype "passive"))
    )
    (net (code "64") (name "Net-(Q19-D)") (class "Default")
      (node (ref "P20") (pin "1") (pinfunction "1_1") (pintype "passive"))
      (node (ref "Q19") (pin "3") (pinfunction "D_3") (pintype "passive"))
    )
    (net (code "65") (name "Net-(Q19-G)") (class "Default")
      (node (ref "Q19") (pin "1") (pinfunction "G_1") (pintype "passive"))
      (node (ref "R18") (pin "1") (pinfunction "1_1") (pintype "passive"))
    )
    (net (code "66") (name "Net-(Q20-D)") (class "Default")
      (node (ref "P21") (pin "1") (pinfunction "1_1") (pintype "passive"))
      (node (ref "Q20") (pin "3") (pinfunction "D_3") (pintype "passive"))
    )
    (net (code "67") (name "Net-(Q20-G)") (class "Default")
      (node (ref "Q20") (pin "1") (pinfunction "G_1") (pintype "passive"))
      (node (ref "R19") (pin "1") (pinfunction "1_1") (pintype "passive"))
    )
    (net (code "68") (name "Net-(Q21-D)") (class "Default")
      (node (ref "P22") (pin "1") (pinfunction "1_1") (pintype "passive"))
      (node (ref "Q21") (pin "3") (pinfunction "D_3") (pintype "passive"))
    )
    (net (code "69") (name "Net-(Q21-G)") (class "Default")
      (node (ref "Q21") (pin "1") (pinfunction "G_1") (pintype "passive"))
      (node (ref "R20") (pin "1") (pinfunction "1_1") (pintype "passive"))
    )
    (net (code "70") (name "Net-(Q22-D)") (class "Default")
      (node (ref "P23") (pin "1") (pinfunction "1_1") (pintype "passive"))
      (node (ref "Q22") (pin "3") (pinfunction "D_3") (pintype "passive"))
    )
    (net (code "71") (name "Net-(Q22-G)") (class "Default")
      (node (ref "Q22") (pin "1") (pinfunction "G_1") (pintype "passive"))
      (node (ref "R21") (pin "1") (pinfunction "1_1") (pintype "passive"))
    )
    (net (code "72") (name "Net-(Q23-D)") (class "Default")
      (node (ref "P24") (pin "1") (pinfunction "1_1") (pintype "passive"))
      (node (ref "Q23") (pin "3") (pinfunction "D_3") (pintype "passive"))
    )
    (net (code "73") (name "Net-(Q23-G)") (class "Default")
      (node (ref "Q23") (pin "1") (pinfunction "G_1") (pintype "passive"))
      (node (ref "R22") (pin "1") (pinfunction "1_1") (pintype "passive"))
    )
    (net (code "74") (name "Net-(RV-WIPER)") (class "Default")
      (node (ref "RV") (pin "2") (pinfunction "WIPER_2") (pintype "passive"))
      (node (ref "U1") (pin "GP28_A2") (pinfunction "GP28_A2_GP28_A2") (pintype "bidirectional"))
    )
    (net (code "75") (name "Net-(VR1-INPUT)") (class "Default")
      (node (ref "C1") (pin "2") (pinfunction "2_2") (pintype "passive"))
      (node (ref "P1") (pin "2") (pinfunction "2_2") (pintype "passive"))
      (node (ref "P10") (pin "2") (pinfunction "2_2") (pintype "passive"))
      (node (ref "P11") (pin "2") (pinfunction "2_2") (pintype "passive"))
      (node (ref "P12") (pin "2") (pinfunction "2_2") (pintype "passive"))
      (node (ref "P13") (pin "2") (pinfunction "2_2") (pintype "passive"))
      (node (ref "P14") (pin "2") (pinfunction "2_2") (pintype "passive"))
      (node (ref "P15") (pin "2") (pinfunction "2_2") (pintype "passive"))
      (node (ref "P16") (pin "2") (pinfunction "2_2") (pintype "passive"))
      (node (ref "P17") (pin "2") (pinfunction "2_2") (pintype "passive"))
      (node (ref "P18") (pin "2") (pinfunction "2_2") (pintype "passive"))
      (node (ref "P19") (pin "2") (pinfunction "2_2") (pintype "passive"))
      (node (ref "P2") (pin "2") (pinfunction "2_2") (pintype "passive"))
      (node (ref "P20") (pin "2") (pinfunction "2_2") (pintype "passive"))
      (node (ref "P21") (pin "2") (pinfunction "2_2") (pintype "passive"))
      (node (ref "P22") (pin "2") (pinfunction "2_2") (pintype "passive"))
      (node (ref "P23") (pin "2") (pinfunction "2_2") (pintype "passive"))
      (node (ref "P24") (pin "2") (pinfunction "2_2") (pintype "passive"))
      (node (ref "P3") (pin "2") (pinfunction "2_2") (pintype "passive"))
      (node (ref "P4") (pin "2") (pinfunction "2_2") (pintype "passive"))
      (node (ref "P5") (pin "2") (pinfunction "2_2") (pintype "passive"))
      (node (ref "P6") (pin "2") (pinfunction "2_2") (pintype "passive"))
      (node (ref "P7") (pin "2") (pinfunction "2_2") (pintype "passive"))
      (node (ref "P8") (pin "2") (pinfunction "2_2") (pintype "passive"))
      (node (ref "P9") (pin "2") (pinfunction "2_2") (pintype "passive"))
      (node (ref "VR1") (pin "1") (pinfunction "INPUT_1") (pintype "input"))
    )
    (net (code "76") (name "Net-(VR1-OUTPUT)") (class "Default")
      (node (ref "C2") (pin "1") (pinfunction "1_1") (pintype "passive"))
      (node (ref "U1") (pin "VSYS") (pinfunction "VSYS_VSYS") (pintype "bidirectional"))
      (node (ref "VR1") (pin "3") (pinfunction "OUTPUT_3") (pintype "output"))
    )
    (net (code "77") (name "unconnected-(U1-Pad3V3_EN)") (class "Default")
      (node (ref "U1") (pin "3V3_EN") (pinfunction "3V3_EN_3V3_EN") (pintype "bidirectional"))
    )
    (net (code "78") (name "unconnected-(U1-PadADC_VREF)") (class "Default")
      (node (ref "U1") (pin "ADC_VREF") (pinfunction "ADC_VREF_ADC_VREF") (pintype "bidirectional"))
    )
    (net (code "79") (name "unconnected-(U1-PadAGND)") (class "Default")
      (node (ref "U1") (pin "AGND") (pinfunction "AGND_AGND") (pintype "bidirectional"))
    )
    (net (code "80") (name "unconnected-(U1-PadGND2)") (class "Default")
      (node (ref "U1") (pin "GND2") (pinfunction "GND2_GND2") (pintype "bidirectional"))
    )
    (net (code "81") (name "unconnected-(U1-PadGND3)") (class "Default")
      (node (ref "U1") (pin "GND3") (pinfunction "GND3_GND3") (pintype "bidirectional"))
    )
    (net (code "82") (name "unconnected-(U1-PadGND4)") (class "Default")
      (node (ref "U1") (pin "GND4") (pinfunction "GND4_GND4") (pintype "bidirectional"))
    )
    (net (code "83") (name "unconnected-(U1-PadGND5)") (class "Default")
      (node (ref "U1") (pin "GND5") (pinfunction "GND5_GND5") (pintype "bidirectional"))
    )
    (net (code "84") (name "unconnected-(U1-PadGND6)") (class "Default")
      (node (ref "U1") (pin "GND6") (pinfunction "GND6_GND6") (pintype "bidirectional"))
    )
    (net (code "85") (name "unconnected-(U1-PadGND7)") (class "Default")
      (node (ref "U1") (pin "GND7") (pinfunction "GND7_GND7") (pintype "bidirectional"))
    )
    (net (code "86") (name "unconnected-(U1-PadRUN)") (class "Default")
      (node (ref "U1") (pin "RUN") (pinfunction "RUN_RUN") (pintype "bidirectional"))
    )
    (net (code "87") (name "unconnected-(U1-PadVBUS)") (class "Default")
      (node (ref "U1") (pin "VBUS") (pinfunction "VBUS_VBUS") (pintype "bidirectional"))
    )
  )
)
